# RMC_Backplane.net
KiCad netlist of a schematic drawn in Altium Designer
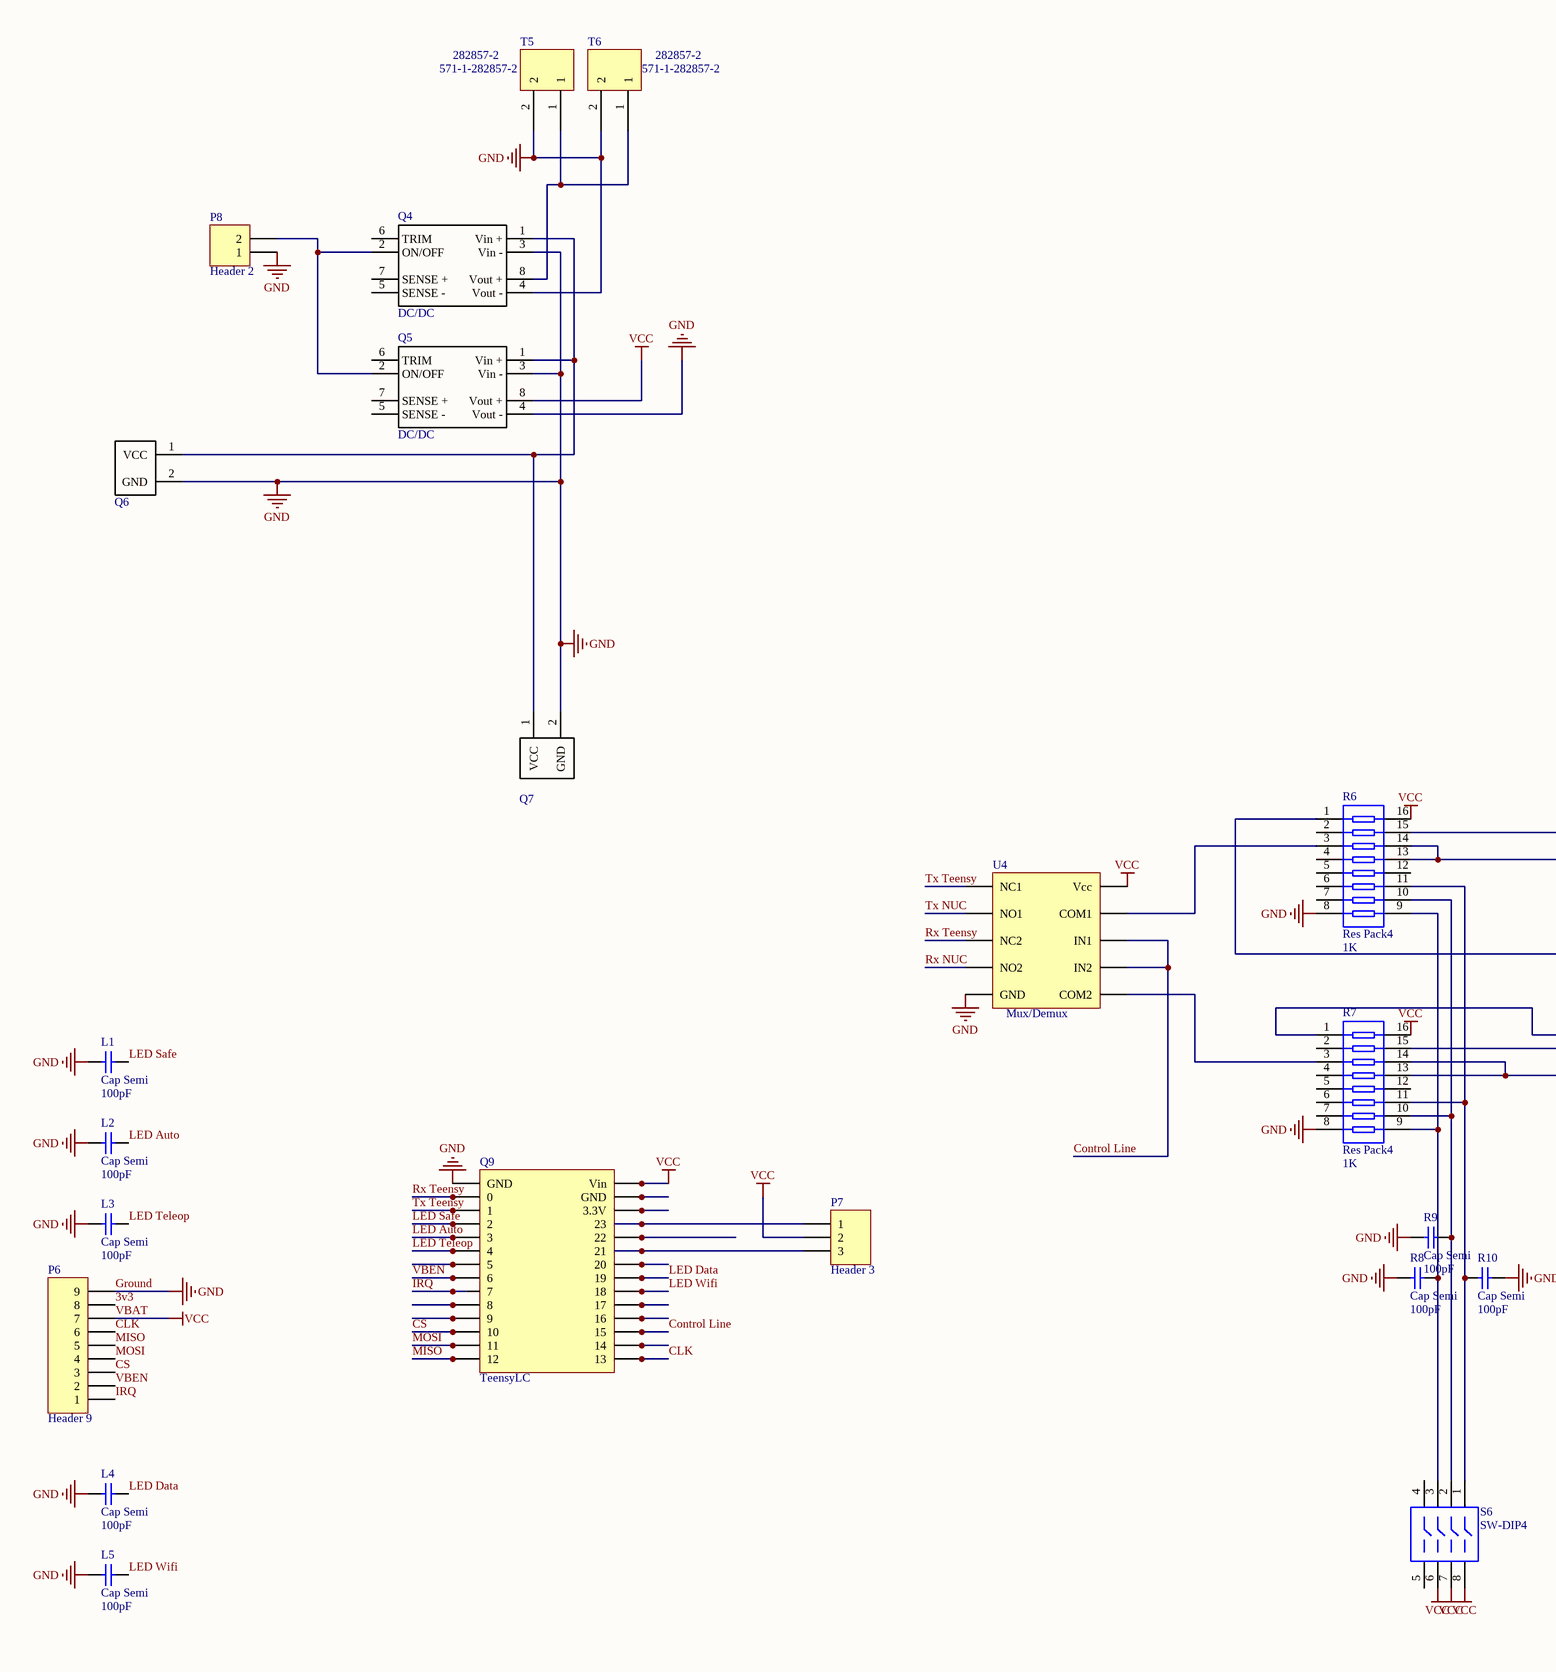
[diagram p0: RMC Backplane.SchDoc, left]
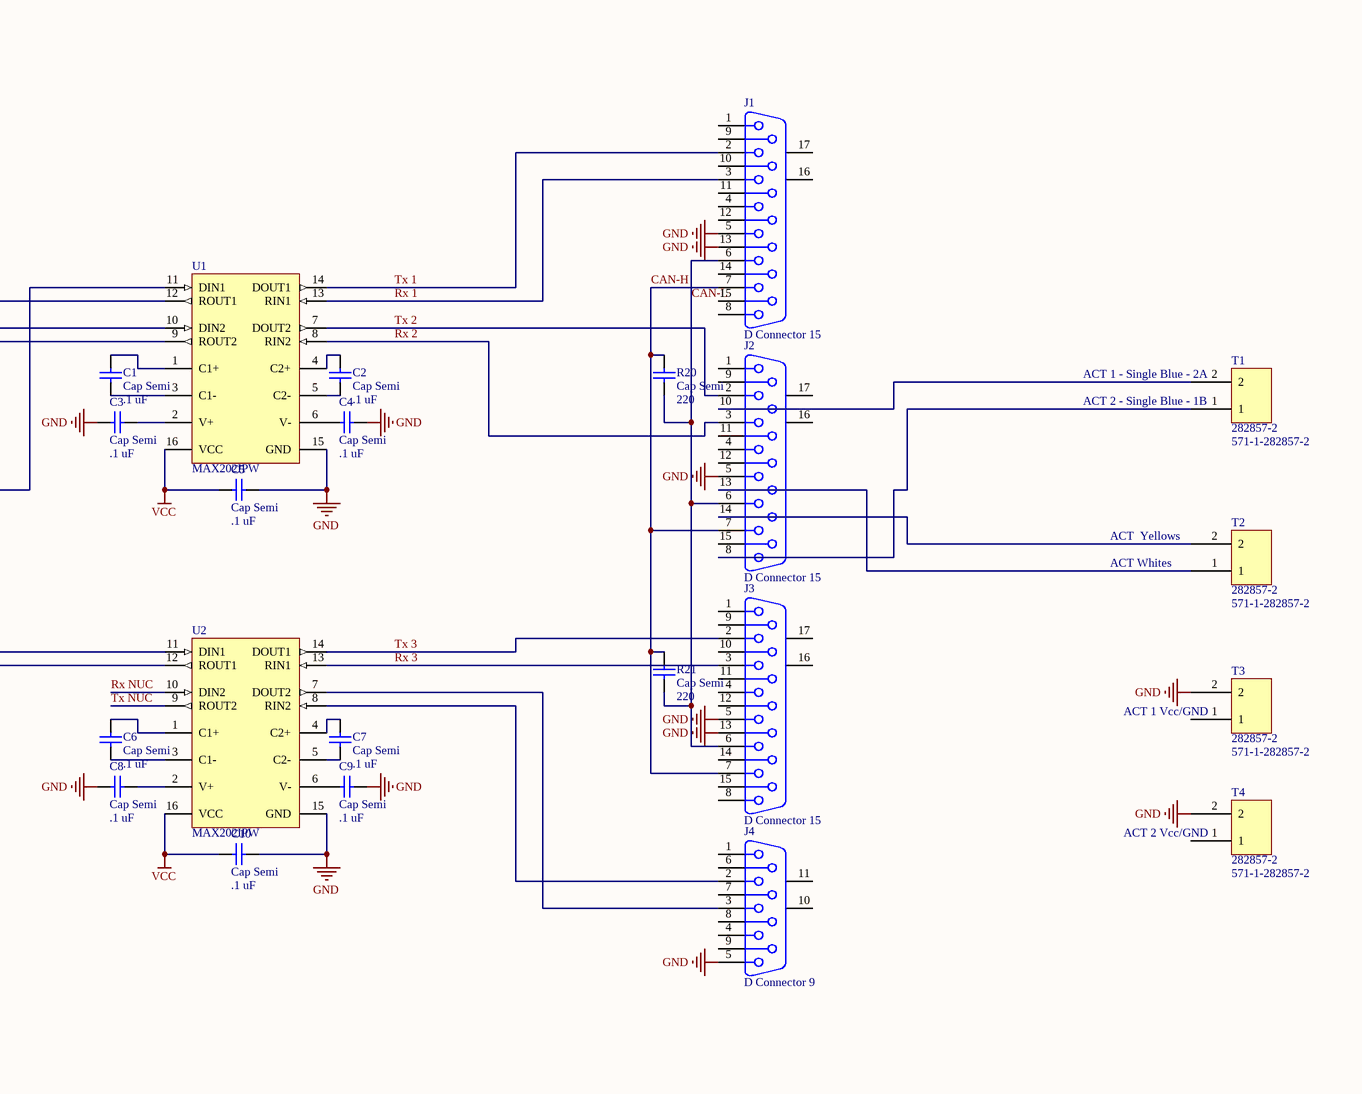
[diagram p1: RMC Backplane.SchDoc, right]

(export (version "E")
  (design (tool "Eeschema 10.0.6"))
  (components
    (comp (ref "C1")
      (value "Cap Semi")
      (footprint "C1206")
      (description "Capacitor (Semiconductor SIM Model)")
      (fields (field (name "ALTIUM_VALUE") ".1 uF") (field (name "PUBLISHER") "Altium Limited"))
      (libsource (lib "Miscellaneous Devices") (part "Cap Semi"))
    )
    (comp (ref "C2")
      (value "Cap Semi")
      (footprint "C1206")
      (description "Capacitor (Semiconductor SIM Model)")
      (fields (field (name "ALTIUM_VALUE") ".1 uF") (field (name "PUBLISHER") "Altium Limited"))
      (libsource (lib "Miscellaneous Devices") (part "Cap Semi"))
    )
    (comp (ref "C3")
      (value "Cap Semi")
      (footprint "C1206")
      (description "Capacitor (Semiconductor SIM Model)")
      (fields (field (name "ALTIUM_VALUE") ".1 uF") (field (name "PUBLISHER") "Altium Limited"))
      (libsource (lib "Miscellaneous Devices") (part "Cap Semi"))
    )
    (comp (ref "C4")
      (value "Cap Semi")
      (footprint "C1206")
      (description "Capacitor (Semiconductor SIM Model)")
      (fields (field (name "ALTIUM_VALUE") ".1 uF") (field (name "PUBLISHER") "Altium Limited"))
      (libsource (lib "Miscellaneous Devices") (part "Cap Semi"))
    )
    (comp (ref "C5")
      (value "Cap Semi")
      (footprint "C1206")
      (description "Capacitor (Semiconductor SIM Model)")
      (fields (field (name "ALTIUM_VALUE") ".1 uF") (field (name "PUBLISHER") "Altium Limited"))
      (libsource (lib "Miscellaneous Devices") (part "Cap Semi"))
    )
    (comp (ref "C6")
      (value "Cap Semi")
      (footprint "C1206")
      (description "Capacitor (Semiconductor SIM Model)")
      (fields (field (name "ALTIUM_VALUE") ".1 uF") (field (name "PUBLISHER") "Altium Limited"))
      (libsource (lib "Miscellaneous Devices") (part "Cap Semi"))
    )
    (comp (ref "C7")
      (value "Cap Semi")
      (footprint "C1206")
      (description "Capacitor (Semiconductor SIM Model)")
      (fields (field (name "ALTIUM_VALUE") ".1 uF") (field (name "PUBLISHER") "Altium Limited"))
      (libsource (lib "Miscellaneous Devices") (part "Cap Semi"))
    )
    (comp (ref "C8")
      (value "Cap Semi")
      (footprint "C1206")
      (description "Capacitor (Semiconductor SIM Model)")
      (fields (field (name "ALTIUM_VALUE") ".1 uF") (field (name "PUBLISHER") "Altium Limited"))
      (libsource (lib "Miscellaneous Devices") (part "Cap Semi"))
    )
    (comp (ref "C9")
      (value "Cap Semi")
      (footprint "C1206")
      (description "Capacitor (Semiconductor SIM Model)")
      (fields (field (name "ALTIUM_VALUE") ".1 uF") (field (name "PUBLISHER") "Altium Limited"))
      (libsource (lib "Miscellaneous Devices") (part "Cap Semi"))
    )
    (comp (ref "C10")
      (value "Cap Semi")
      (footprint "C1206")
      (description "Capacitor (Semiconductor SIM Model)")
      (fields (field (name "ALTIUM_VALUE") ".1 uF") (field (name "PUBLISHER") "Altium Limited"))
      (libsource (lib "Miscellaneous Devices") (part "Cap Semi"))
    )
    (comp (ref "J1")
      (value "D Connector 15")
      (footprint "DSUB1.385-2H15")
      (description "Receptacle Assembly, 15 Position, Right Angle")
      (fields (field (name "PUBLISHER") "Altium Limited"))
      (libsource (lib "Miscellaneous Connectors") (part "D Connector 15"))
    )
    (comp (ref "J2")
      (value "D Connector 15")
      (footprint "DSUB1.385-2H15")
      (description "Receptacle Assembly, 15 Position, Right Angle")
      (fields (field (name "PUBLISHER") "Altium Limited"))
      (libsource (lib "Miscellaneous Connectors") (part "D Connector 15"))
    )
    (comp (ref "J3")
      (value "D Connector 15")
      (footprint "DSUB1.385-2H15")
      (description "Receptacle Assembly, 15 Position, Right Angle")
      (fields (field (name "PUBLISHER") "Altium Limited"))
      (libsource (lib "Miscellaneous Connectors") (part "D Connector 15"))
    )
    (comp (ref "J4")
      (value "D Connector 9")
      (footprint "DSUB1.385-2H9")
      (description "Receptacle Assembly, 9 Position, Right Angle")
      (fields (field (name "PUBLISHER") "Altium Limited"))
      (libsource (lib "Miscellaneous Connectors") (part "D Connector 9"))
    )
    (comp (ref "L1")
      (value "Cap Semi")
      (footprint "C1206")
      (description "Capacitor (Semiconductor SIM Model)")
      (fields (field (name "ALTIUM_VALUE") "100pF") (field (name "PUBLISHER") "Altium Limited"))
      (libsource (lib "Miscellaneous Devices") (part "Cap Semi"))
    )
    (comp (ref "L2")
      (value "Cap Semi")
      (footprint "C1206")
      (description "Capacitor (Semiconductor SIM Model)")
      (fields (field (name "ALTIUM_VALUE") "100pF") (field (name "PUBLISHER") "Altium Limited"))
      (libsource (lib "Miscellaneous Devices") (part "Cap Semi"))
    )
    (comp (ref "L3")
      (value "Cap Semi")
      (footprint "C1206")
      (description "Capacitor (Semiconductor SIM Model)")
      (fields (field (name "ALTIUM_VALUE") "100pF") (field (name "PUBLISHER") "Altium Limited"))
      (libsource (lib "Miscellaneous Devices") (part "Cap Semi"))
    )
    (comp (ref "L4")
      (value "Cap Semi")
      (footprint "C1206")
      (description "Capacitor (Semiconductor SIM Model)")
      (fields (field (name "ALTIUM_VALUE") "100pF") (field (name "PUBLISHER") "Altium Limited"))
      (libsource (lib "Miscellaneous Devices") (part "Cap Semi"))
    )
    (comp (ref "L5")
      (value "Cap Semi")
      (footprint "C1206")
      (description "Capacitor (Semiconductor SIM Model)")
      (fields (field (name "ALTIUM_VALUE") "100pF") (field (name "PUBLISHER") "Altium Limited"))
      (libsource (lib "Miscellaneous Devices") (part "Cap Semi"))
    )
    (comp (ref "P6")
      (value "Header 9")
      (footprint "HDR1X9")
      (description "Header, 9-Pin")
      (fields (field (name "PUBLISHER") "Altium Limited"))
      (libsource (lib "Miscellaneous Connectors") (part "Header 9"))
    )
    (comp (ref "P7")
      (value "Header 3")
      (footprint "HDR1X3")
      (description "Header, 3-Pin")
      (fields (field (name "PUBLISHER") "Altium Limited"))
      (libsource (lib "Miscellaneous Connectors") (part "Header 3"))
    )
    (comp (ref "P8")
      (value "Header 2")
      (footprint "HDR1X2")
      (description "Header, 2-Pin")
      (fields (field (name "PUBLISHER") "Altium Limited"))
      (libsource (lib "Miscellaneous Connectors") (part "Header 2"))
    )
    (comp (ref "Q4")
      (value "DC/DC")
      (footprint "EHHD")
      (description "Voltage Regulator")
      (libsource (lib "Custom_Components") (part "EHHD"))
    )
    (comp (ref "Q5")
      (value "DC/DC")
      (footprint "EHHD")
      (description "Voltage Regulator")
      (libsource (lib "Custom_Components") (part "EHHD"))
    )
    (comp (ref "Q6")
      (value "Power Conn")
      (footprint "Mini-Fit Power Conn")
      (description "Mini-Fit Molex Connector")
      (libsource (lib "Custom_Schematics") (part "Mini-Fit Power Conn"))
    )
    (comp (ref "Q7")
      (value "Power Conn")
      (footprint "Mini-Fit Power Conn")
      (description "Mini-Fit Molex Connector")
      (libsource (lib "Custom_Schematics") (part "Mini-Fit Power Conn"))
    )
    (comp (ref "Q9")
      (value "TeensyLC")
      (footprint "TeensyLC")
      (libsource (lib "Custom_Schematics") (part "TeensyLC"))
    )
    (comp (ref "R6")
      (value "Res Pack4")
      (footprint "SSOP16_N")
      (description "Isolated Resistor Network")
      (fields (field (name "ALTIUM_VALUE") "1K") (field (name "PUBLISHER") "Altium Limited"))
      (libsource (lib "Miscellaneous Devices") (part "Res Pack4"))
    )
    (comp (ref "R7")
      (value "Res Pack4")
      (footprint "SSOP16_N")
      (description "Isolated Resistor Network")
      (fields (field (name "ALTIUM_VALUE") "1K") (field (name "PUBLISHER") "Altium Limited"))
      (libsource (lib "Miscellaneous Devices") (part "Res Pack4"))
    )
    (comp (ref "R8")
      (value "Cap Semi")
      (footprint "C1206")
      (description "Capacitor (Semiconductor SIM Model)")
      (fields (field (name "ALTIUM_VALUE") "100pF") (field (name "PUBLISHER") "Altium Limited"))
      (libsource (lib "Miscellaneous Devices") (part "Cap Semi"))
    )
    (comp (ref "R9")
      (value "Cap Semi")
      (footprint "C1206")
      (description "Capacitor (Semiconductor SIM Model)")
      (fields (field (name "ALTIUM_VALUE") "100pF") (field (name "PUBLISHER") "Altium Limited"))
      (libsource (lib "Miscellaneous Devices") (part "Cap Semi"))
    )
    (comp (ref "R10")
      (value "Cap Semi")
      (footprint "C1206")
      (description "Capacitor (Semiconductor SIM Model)")
      (fields (field (name "ALTIUM_VALUE") "100pF") (field (name "PUBLISHER") "Altium Limited"))
      (libsource (lib "Miscellaneous Devices") (part "Cap Semi"))
    )
    (comp (ref "R20")
      (value "Cap Semi")
      (footprint "C1206")
      (description "Capacitor (Semiconductor SIM Model)")
      (fields (field (name "ALTIUM_VALUE") "220") (field (name "PUBLISHER") "Altium Limited"))
      (libsource (lib "Miscellaneous Devices") (part "Cap Semi"))
    )
    (comp (ref "R21")
      (value "Cap Semi")
      (footprint "C1206")
      (description "Capacitor (Semiconductor SIM Model)")
      (fields (field (name "ALTIUM_VALUE") "220") (field (name "PUBLISHER") "Altium Limited"))
      (libsource (lib "Miscellaneous Devices") (part "Cap Semi"))
    )
    (comp (ref "S6")
      (value "SW-DIP4")
      (footprint "DIP-8")
      (description "DIP Switch")
      (fields (field (name "PUBLISHER") "Altium Limited"))
      (libsource (lib "Miscellaneous Devices") (part "SW-DIP4"))
    )
    (comp (ref "T1")
      (value "282857-2")
      (footprint "282857-2")
      (fields (field (name "SUPPLIER PART NUMBER 1") "571-1-282857-2"))
      (libsource (lib "") (part "282857-2_1"))
    )
    (comp (ref "T2")
      (value "282857-2")
      (footprint "282857-2")
      (fields (field (name "SUPPLIER PART NUMBER 1") "571-1-282857-2"))
      (libsource (lib "") (part "282857-2_1"))
    )
    (comp (ref "T3")
      (value "282857-2")
      (footprint "282857-2")
      (fields (field (name "SUPPLIER PART NUMBER 1") "571-1-282857-2"))
      (libsource (lib "") (part "282857-2_1"))
    )
    (comp (ref "T4")
      (value "282857-2")
      (footprint "282857-2")
      (fields (field (name "SUPPLIER PART NUMBER 1") "571-1-282857-2"))
      (libsource (lib "") (part "282857-2_1"))
    )
    (comp (ref "T5")
      (value "282857-2")
      (footprint "282857-2")
      (fields (field (name "SUPPLIER PART NUMBER 1") "571-1-282857-2"))
      (libsource (lib "TE_Connectors") (part "282857-2"))
    )
    (comp (ref "T6")
      (value "282857-2")
      (footprint "282857-2")
      (fields (field (name "SUPPLIER PART NUMBER 1") "571-1-282857-2"))
      (libsource (lib "TE_Connectors") (part "282857-2"))
    )
    (comp (ref "U1")
      (value "MAX202IPW")
      (footprint "TI-PW16_N")
      (libsource (lib "Texas Instruments Interface RS-232") (part "MAX202IPW"))
    )
    (comp (ref "U2")
      (value "MAX202IPW")
      (footprint "TI-PW16_N")
      (libsource (lib "Texas Instruments Interface RS-232") (part "MAX202IPW"))
    )
    (comp (ref "U4")
      (value "Mux/Demux")
      (footprint "TS3A24157")
      (libsource (lib "Custom_Schematics") (part "Mux/Demux"))
    )
  )
  (nets
    (net (code "1") (name "/3v3") (class "Default")
      (node (ref "P6") (pin "8") (pinfunction "8_8") (pintype "passive"))
    )
    (net (code "2") (name "/CAN-H") (class "Default")
      (node (ref "J1") (pin "7") (pinfunction "7_7") (pintype "passive"))
      (node (ref "J2") (pin "7") (pinfunction "7_7") (pintype "passive"))
      (node (ref "J3") (pin "7") (pinfunction "7_7") (pintype "passive"))
      (node (ref "R20") (pin "1") (pinfunction "1_1") (pintype "passive"))
      (node (ref "R21") (pin "1") (pinfunction "1_1") (pintype "passive"))
    )
    (net (code "3") (name "/CAN-L") (class "Default")
      (node (ref "J1") (pin "6") (pinfunction "6_6") (pintype "passive"))
      (node (ref "J2") (pin "6") (pinfunction "6_6") (pintype "passive"))
      (node (ref "J3") (pin "6") (pinfunction "6_6") (pintype "passive"))
      (node (ref "R20") (pin "2") (pinfunction "2_2") (pintype "passive"))
      (node (ref "R21") (pin "2") (pinfunction "2_2") (pintype "passive"))
    )
    (net (code "4") (name "/CLK") (class "Default")
      (node (ref "P6") (pin "6") (pinfunction "6_6") (pintype "passive"))
      (node (ref "Q9") (pin "15") (pinfunction "13_15") (pintype "passive"))
    )
    (net (code "5") (name "/CS") (class "Default")
      (node (ref "P6") (pin "3") (pinfunction "3_3") (pintype "passive"))
      (node (ref "Q9") (pin "12") (pinfunction "10_12") (pintype "passive"))
    )
    (net (code "6") (name "/Control Line") (class "Default")
      (node (ref "Q9") (pin "17") (pinfunction "15_17") (pintype "passive"))
      (node (ref "U4") (pin "7") (pinfunction "IN2_7") (pintype "passive"))
      (node (ref "U4") (pin "8") (pinfunction "IN1_8") (pintype "passive"))
    )
    (net (code "7") (name "/IRQ") (class "Default")
      (node (ref "P6") (pin "1") (pinfunction "1_1") (pintype "passive"))
      (node (ref "Q9") (pin "9") (pinfunction "7_9") (pintype "passive"))
    )
    (net (code "8") (name "/LED Auto") (class "Default")
      (node (ref "L2") (pin "2") (pinfunction "2_2") (pintype "passive"))
      (node (ref "Q9") (pin "5") (pinfunction "3_5") (pintype "passive"))
    )
    (net (code "9") (name "/LED Data") (class "Default")
      (node (ref "L4") (pin "2") (pinfunction "2_2") (pintype "passive"))
      (node (ref "Q9") (pin "21") (pinfunction "19_21") (pintype "passive"))
    )
    (net (code "10") (name "/LED Safe") (class "Default")
      (node (ref "L1") (pin "2") (pinfunction "2_2") (pintype "passive"))
      (node (ref "Q9") (pin "4") (pinfunction "2_4") (pintype "passive"))
    )
    (net (code "11") (name "/LED Teleop") (class "Default")
      (node (ref "L3") (pin "2") (pinfunction "2_2") (pintype "passive"))
      (node (ref "Q9") (pin "6") (pinfunction "4_6") (pintype "passive"))
    )
    (net (code "12") (name "/LED Wifi") (class "Default")
      (node (ref "L5") (pin "2") (pinfunction "2_2") (pintype "passive"))
      (node (ref "Q9") (pin "20") (pinfunction "18_20") (pintype "passive"))
    )
    (net (code "13") (name "/MISO") (class "Default")
      (node (ref "P6") (pin "5") (pinfunction "5_5") (pintype "passive"))
      (node (ref "Q9") (pin "14") (pinfunction "12_14") (pintype "passive"))
    )
    (net (code "14") (name "/MOSI") (class "Default")
      (node (ref "P6") (pin "4") (pinfunction "4_4") (pintype "passive"))
      (node (ref "Q9") (pin "13") (pinfunction "11_13") (pintype "passive"))
    )
    (net (code "15") (name "/Rx 1") (class "Default")
      (node (ref "J1") (pin "3") (pinfunction "3_3") (pintype "passive"))
      (node (ref "U1") (pin "13") (pinfunction "RIN1_13") (pintype "input"))
    )
    (net (code "16") (name "/Rx 2") (class "Default")
      (node (ref "J2") (pin "3") (pinfunction "3_3") (pintype "passive"))
      (node (ref "U1") (pin "8") (pinfunction "RIN2_8") (pintype "input"))
    )
    (net (code "17") (name "/Rx 3") (class "Default")
      (node (ref "J3") (pin "3") (pinfunction "3_3") (pintype "passive"))
      (node (ref "U2") (pin "13") (pinfunction "RIN1_13") (pintype "input"))
    )
    (net (code "18") (name "/Rx NUC") (class "Default")
      (node (ref "U2") (pin "10") (pinfunction "DIN2_10") (pintype "input"))
      (node (ref "U4") (pin "4") (pinfunction "NO2_4") (pintype "passive"))
    )
    (net (code "19") (name "/Rx Teensy") (class "Default")
      (node (ref "Q9") (pin "2") (pinfunction "0_2") (pintype "passive"))
      (node (ref "U4") (pin "3") (pinfunction "NC2_3") (pintype "passive"))
    )
    (net (code "20") (name "/Tx 1") (class "Default")
      (node (ref "J1") (pin "2") (pinfunction "2_2") (pintype "passive"))
      (node (ref "U1") (pin "14") (pinfunction "DOUT1_14") (pintype "output"))
    )
    (net (code "21") (name "/Tx 2") (class "Default")
      (node (ref "J2") (pin "2") (pinfunction "2_2") (pintype "passive"))
      (node (ref "U1") (pin "7") (pinfunction "DOUT2_7") (pintype "output"))
    )
    (net (code "22") (name "/Tx 3") (class "Default")
      (node (ref "J3") (pin "2") (pinfunction "2_2") (pintype "passive"))
      (node (ref "U2") (pin "14") (pinfunction "DOUT1_14") (pintype "output"))
    )
    (net (code "23") (name "/Tx NUC") (class "Default")
      (node (ref "U2") (pin "9") (pinfunction "ROUT2_9") (pintype "output"))
      (node (ref "U4") (pin "2") (pinfunction "NO1_2") (pintype "passive"))
    )
    (net (code "24") (name "/Tx Teensy") (class "Default")
      (node (ref "Q9") (pin "3") (pinfunction "1_3") (pintype "passive"))
      (node (ref "U4") (pin "1") (pinfunction "NC1_1") (pintype "passive"))
    )
    (net (code "25") (name "/VBEN") (class "Default")
      (node (ref "P6") (pin "2") (pinfunction "2_2") (pintype "passive"))
      (node (ref "Q9") (pin "8") (pinfunction "6_8") (pintype "passive"))
    )
    (net (code "26") (name "GND") (class "Default")
      (node (ref "C10") (pin "2") (pinfunction "2_2") (pintype "passive"))
      (node (ref "C3") (pin "1") (pinfunction "1_1") (pintype "passive"))
      (node (ref "C4") (pin "2") (pinfunction "2_2") (pintype "passive"))
      (node (ref "C5") (pin "2") (pinfunction "2_2") (pintype "passive"))
      (node (ref "C8") (pin "1") (pinfunction "1_1") (pintype "passive"))
      (node (ref "C9") (pin "2") (pinfunction "2_2") (pintype "passive"))
      (node (ref "J1") (pin "13") (pinfunction "13_13") (pintype "passive"))
      (node (ref "J1") (pin "5") (pinfunction "5_5") (pintype "passive"))
      (node (ref "J2") (pin "5") (pinfunction "5_5") (pintype "passive"))
      (node (ref "J3") (pin "13") (pinfunction "13_13") (pintype "passive"))
      (node (ref "J3") (pin "5") (pinfunction "5_5") (pintype "passive"))
      (node (ref "J4") (pin "5") (pinfunction "5_5") (pintype "passive"))
      (node (ref "L1") (pin "1") (pinfunction "1_1") (pintype "passive"))
      (node (ref "L2") (pin "1") (pinfunction "1_1") (pintype "passive"))
      (node (ref "L3") (pin "1") (pinfunction "1_1") (pintype "passive"))
      (node (ref "L4") (pin "1") (pinfunction "1_1") (pintype "passive"))
      (node (ref "L5") (pin "1") (pinfunction "1_1") (pintype "passive"))
      (node (ref "P6") (pin "9") (pinfunction "9_9") (pintype "passive"))
      (node (ref "P8") (pin "1") (pinfunction "1_1") (pintype "passive"))
      (node (ref "Q4") (pin "3") (pinfunction "Vin_-_3") (pintype "passive"))
      (node (ref "Q4") (pin "4") (pinfunction "Vout_-_4") (pintype "power_in"))
      (node (ref "Q5") (pin "3") (pinfunction "Vin_-_3") (pintype "passive"))
      (node (ref "Q5") (pin "4") (pinfunction "Vout_-_4") (pintype "power_in"))
      (node (ref "Q6") (pin "2") (pinfunction "GND_2") (pintype "power_in"))
      (node (ref "Q7") (pin "2") (pinfunction "GND_2") (pintype "power_in"))
      (node (ref "Q9") (pin "1") (pinfunction "GND_1") (pintype "passive"))
      (node (ref "R10") (pin "2") (pinfunction "2_2") (pintype "passive"))
      (node (ref "R6") (pin "8") (pinfunction "8_8") (pintype "passive"))
      (node (ref "R7") (pin "8") (pinfunction "8_8") (pintype "passive"))
      (node (ref "R8") (pin "1") (pinfunction "1_1") (pintype "passive"))
      (node (ref "R9") (pin "1") (pinfunction "1_1") (pintype "passive"))
      (node (ref "T3") (pin "2") (pinfunction "2_2") (pintype "passive"))
      (node (ref "T4") (pin "2") (pinfunction "2_2") (pintype "passive"))
      (node (ref "T5") (pin "2") (pinfunction "2_2") (pintype "passive"))
      (node (ref "T6") (pin "2") (pinfunction "2_2") (pintype "passive"))
      (node (ref "U1") (pin "15") (pinfunction "GND_15") (pintype "power_in"))
      (node (ref "U2") (pin "15") (pinfunction "GND_15") (pintype "power_in"))
      (node (ref "U4") (pin "5") (pinfunction "GND_5") (pintype "passive"))
    )
    (net (code "27") (name "Net-(J2-Pad8)") (class "Default")
      (node (ref "J2") (pin "8") (pinfunction "8_8") (pintype "passive"))
      (node (ref "T1") (pin "1") (pinfunction "1_1") (pintype "passive"))
    )
    (net (code "28") (name "Net-(J2-Pad10)") (class "Default")
      (node (ref "J2") (pin "10") (pinfunction "10_10") (pintype "passive"))
      (node (ref "T1") (pin "2") (pinfunction "2_2") (pintype "passive"))
    )
    (net (code "29") (name "Net-(J2-Pad13)") (class "Default")
      (node (ref "J2") (pin "13") (pinfunction "13_13") (pintype "passive"))
      (node (ref "T2") (pin "1") (pinfunction "1_1") (pintype "passive"))
    )
    (net (code "30") (name "Net-(J2-Pad14)") (class "Default")
      (node (ref "J2") (pin "14") (pinfunction "14_14") (pintype "passive"))
      (node (ref "T2") (pin "2") (pinfunction "2_2") (pintype "passive"))
    )
    (net (code "31") (name "Net-(Q4-ON{slash}OFF)") (class "Default")
      (node (ref "P8") (pin "2") (pinfunction "2_2") (pintype "passive"))
      (node (ref "Q4") (pin "2") (pinfunction "ON/OFF_2") (pintype "passive"))
      (node (ref "Q5") (pin "2") (pinfunction "ON/OFF_2") (pintype "passive"))
    )
    (net (code "32") (name "Net-(Q4-Vin_+)") (class "Default")
      (node (ref "Q4") (pin "1") (pinfunction "Vin_+_1") (pintype "passive"))
      (node (ref "Q5") (pin "1") (pinfunction "Vin_+_1") (pintype "passive"))
      (node (ref "Q6") (pin "1") (pinfunction "VCC_1") (pintype "power_in"))
      (node (ref "Q7") (pin "1") (pinfunction "VCC_1") (pintype "power_in"))
    )
    (net (code "33") (name "Net-(Q4-Vout_+)") (class "Default")
      (node (ref "Q4") (pin "8") (pinfunction "Vout_+_8") (pintype "power_in"))
      (node (ref "T5") (pin "1") (pinfunction "1_1") (pintype "passive"))
      (node (ref "T6") (pin "1") (pinfunction "1_1") (pintype "passive"))
    )
    (net (code "34") (name "Net-(Q9-21)") (class "Default")
      (node (ref "P7") (pin "3") (pinfunction "3_3") (pintype "passive"))
      (node (ref "Q9") (pin "23") (pinfunction "21_23") (pintype "passive"))
    )
    (net (code "35") (name "Net-(Q9-23)") (class "Default")
      (node (ref "P7") (pin "1") (pinfunction "1_1") (pintype "passive"))
      (node (ref "Q9") (pin "25") (pinfunction "23_25") (pintype "passive"))
    )
    (net (code "36") (name "Net-(R6-Pad9)") (class "Default")
      (node (ref "R6") (pin "9") (pinfunction "9_9") (pintype "passive"))
      (node (ref "R7") (pin "9") (pinfunction "9_9") (pintype "passive"))
      (node (ref "R8") (pin "2") (pinfunction "2_2") (pintype "passive"))
      (node (ref "S6") (pin "3") (pinfunction "3_3") (pintype "passive"))
    )
    (net (code "37") (name "Net-(R6-Pad10)") (class "Default")
      (node (ref "R6") (pin "10") (pinfunction "10_10") (pintype "passive"))
      (node (ref "R7") (pin "10") (pinfunction "10_10") (pintype "passive"))
      (node (ref "R9") (pin "2") (pinfunction "2_2") (pintype "passive"))
      (node (ref "S6") (pin "2") (pinfunction "2_2") (pintype "passive"))
    )
    (net (code "38") (name "Net-(R10-Pad1)") (class "Default")
      (node (ref "R10") (pin "1") (pinfunction "1_1") (pintype "passive"))
      (node (ref "R6") (pin "11") (pinfunction "11_11") (pintype "passive"))
      (node (ref "R7") (pin "11") (pinfunction "11_11") (pintype "passive"))
      (node (ref "S6") (pin "1") (pinfunction "1_1") (pintype "passive"))
    )
    (net (code "39") (name "Net-(U1-C1+)") (class "Default")
      (node (ref "C1") (pin "1") (pinfunction "1_1") (pintype "passive"))
      (node (ref "U1") (pin "1") (pinfunction "C1+_1") (pintype "passive"))
    )
    (net (code "40") (name "Net-(U1-C1-)") (class "Default")
      (node (ref "C1") (pin "2") (pinfunction "2_2") (pintype "passive"))
      (node (ref "U1") (pin "3") (pinfunction "C1-_3") (pintype "passive"))
    )
    (net (code "41") (name "Net-(U1-C2+)") (class "Default")
      (node (ref "C2") (pin "1") (pinfunction "1_1") (pintype "passive"))
      (node (ref "U1") (pin "4") (pinfunction "C2+_4") (pintype "passive"))
    )
    (net (code "42") (name "Net-(U1-C2-)") (class "Default")
      (node (ref "C2") (pin "2") (pinfunction "2_2") (pintype "passive"))
      (node (ref "U1") (pin "5") (pinfunction "C2-_5") (pintype "passive"))
    )
    (net (code "43") (name "Net-(U1-DIN1)") (class "Default")
      (node (ref "R6") (pin "13") (pinfunction "13_13") (pintype "passive"))
      (node (ref "R6") (pin "14") (pinfunction "14_14") (pintype "passive"))
      (node (ref "U1") (pin "11") (pinfunction "DIN1_11") (pintype "input"))
    )
    (net (code "44") (name "Net-(U1-DIN2)") (class "Default")
      (node (ref "R6") (pin "15") (pinfunction "15_15") (pintype "passive"))
      (node (ref "U1") (pin "10") (pinfunction "DIN2_10") (pintype "input"))
    )
    (net (code "45") (name "Net-(U1-ROUT1)") (class "Default")
      (node (ref "R7") (pin "13") (pinfunction "13_13") (pintype "passive"))
      (node (ref "R7") (pin "14") (pinfunction "14_14") (pintype "passive"))
      (node (ref "U1") (pin "12") (pinfunction "ROUT1_12") (pintype "output"))
    )
    (net (code "46") (name "Net-(U1-ROUT2)") (class "Default")
      (node (ref "R7") (pin "15") (pinfunction "15_15") (pintype "passive"))
      (node (ref "U1") (pin "9") (pinfunction "ROUT2_9") (pintype "output"))
    )
    (net (code "47") (name "Net-(U1-V+)") (class "Default")
      (node (ref "C3") (pin "2") (pinfunction "2_2") (pintype "passive"))
      (node (ref "U1") (pin "2") (pinfunction "V+_2") (pintype "power_in"))
    )
    (net (code "48") (name "Net-(U1-V-)") (class "Default")
      (node (ref "C4") (pin "1") (pinfunction "1_1") (pintype "passive"))
      (node (ref "U1") (pin "6") (pinfunction "V-_6") (pintype "power_in"))
    )
    (net (code "49") (name "Net-(U2-C1+)") (class "Default")
      (node (ref "C6") (pin "1") (pinfunction "1_1") (pintype "passive"))
      (node (ref "U2") (pin "1") (pinfunction "C1+_1") (pintype "passive"))
    )
    (net (code "50") (name "Net-(U2-C1-)") (class "Default")
      (node (ref "C6") (pin "2") (pinfunction "2_2") (pintype "passive"))
      (node (ref "U2") (pin "3") (pinfunction "C1-_3") (pintype "passive"))
    )
    (net (code "51") (name "Net-(U2-C2+)") (class "Default")
      (node (ref "C7") (pin "1") (pinfunction "1_1") (pintype "passive"))
      (node (ref "U2") (pin "4") (pinfunction "C2+_4") (pintype "passive"))
    )
    (net (code "52") (name "Net-(U2-C2-)") (class "Default")
      (node (ref "C7") (pin "2") (pinfunction "2_2") (pintype "passive"))
      (node (ref "U2") (pin "5") (pinfunction "C2-_5") (pintype "passive"))
    )
    (net (code "53") (name "Net-(U2-DIN1)") (class "Default")
      (node (ref "R6") (pin "1") (pinfunction "1_1") (pintype "passive"))
      (node (ref "U2") (pin "11") (pinfunction "DIN1_11") (pintype "input"))
    )
    (net (code "54") (name "Net-(U2-DOUT2)") (class "Default")
      (node (ref "J4") (pin "3") (pinfunction "3_3") (pintype "passive"))
      (node (ref "U2") (pin "7") (pinfunction "DOUT2_7") (pintype "output"))
    )
    (net (code "55") (name "Net-(U2-RIN2)") (class "Default")
      (node (ref "J4") (pin "2") (pinfunction "2_2") (pintype "passive"))
      (node (ref "U2") (pin "8") (pinfunction "RIN2_8") (pintype "input"))
    )
    (net (code "56") (name "Net-(U2-ROUT1)") (class "Default")
      (node (ref "R7") (pin "1") (pinfunction "1_1") (pintype "passive"))
      (node (ref "U2") (pin "12") (pinfunction "ROUT1_12") (pintype "output"))
    )
    (net (code "57") (name "Net-(U2-V+)") (class "Default")
      (node (ref "C8") (pin "2") (pinfunction "2_2") (pintype "passive"))
      (node (ref "U2") (pin "2") (pinfunction "V+_2") (pintype "power_in"))
    )
    (net (code "58") (name "Net-(U2-V-)") (class "Default")
      (node (ref "C9") (pin "1") (pinfunction "1_1") (pintype "passive"))
      (node (ref "U2") (pin "6") (pinfunction "V-_6") (pintype "power_in"))
    )
    (net (code "59") (name "Net-(U4-COM1)") (class "Default")
      (node (ref "R6") (pin "3") (pinfunction "3_3") (pintype "passive"))
      (node (ref "U4") (pin "9") (pinfunction "COM1_9") (pintype "passive"))
    )
    (net (code "60") (name "Net-(U4-COM2)") (class "Default")
      (node (ref "R7") (pin "3") (pinfunction "3_3") (pintype "passive"))
      (node (ref "U4") (pin "6") (pinfunction "COM2_6") (pintype "passive"))
    )
    (net (code "61") (name "VCC") (class "Default")
      (node (ref "C10") (pin "1") (pinfunction "1_1") (pintype "passive"))
      (node (ref "C5") (pin "1") (pinfunction "1_1") (pintype "passive"))
      (node (ref "P6") (pin "7") (pinfunction "7_7") (pintype "passive"))
      (node (ref "P7") (pin "2") (pinfunction "2_2") (pintype "passive"))
      (node (ref "Q5") (pin "8") (pinfunction "Vout_+_8") (pintype "power_in"))
      (node (ref "Q9") (pin "28") (pinfunction "Vin_28") (pintype "passive"))
      (node (ref "R6") (pin "16") (pinfunction "16_16") (pintype "passive"))
      (node (ref "R7") (pin "16") (pinfunction "16_16") (pintype "passive"))
      (node (ref "S6") (pin "6") (pinfunction "6_6") (pintype "passive"))
      (node (ref "S6") (pin "7") (pinfunction "7_7") (pintype "passive"))
      (node (ref "S6") (pin "8") (pinfunction "8_8") (pintype "passive"))
      (node (ref "U1") (pin "16") (pinfunction "VCC_16") (pintype "power_in"))
      (node (ref "U2") (pin "16") (pinfunction "VCC_16") (pintype "power_in"))
      (node (ref "U4") (pin "10") (pinfunction "Vcc_10") (pintype "passive"))
    )
    (net (code "62") (name "unconnected-(J1-MH1-Pad16)") (class "Default")
      (node (ref "J1") (pin "16") (pinfunction "MH1_16") (pintype "passive"))
    )
    (net (code "63") (name "unconnected-(J1-MH2-Pad17)") (class "Default")
      (node (ref "J1") (pin "17") (pinfunction "MH2_17") (pintype "passive"))
    )
    (net (code "64") (name "unconnected-(J1-Pad1)") (class "Default")
      (node (ref "J1") (pin "1") (pinfunction "1_1") (pintype "passive"))
    )
    (net (code "65") (name "unconnected-(J1-Pad4)") (class "Default")
      (node (ref "J1") (pin "4") (pinfunction "4_4") (pintype "passive"))
    )
    (net (code "66") (name "unconnected-(J1-Pad8)") (class "Default")
      (node (ref "J1") (pin "8") (pinfunction "8_8") (pintype "passive"))
    )
    (net (code "67") (name "unconnected-(J1-Pad9)") (class "Default")
      (node (ref "J1") (pin "9") (pinfunction "9_9") (pintype "passive"))
    )
    (net (code "68") (name "unconnected-(J1-Pad10)") (class "Default")
      (node (ref "J1") (pin "10") (pinfunction "10_10") (pintype "passive"))
    )
    (net (code "69") (name "unconnected-(J1-Pad11)") (class "Default")
      (node (ref "J1") (pin "11") (pinfunction "11_11") (pintype "passive"))
    )
    (net (code "70") (name "unconnected-(J1-Pad12)") (class "Default")
      (node (ref "J1") (pin "12") (pinfunction "12_12") (pintype "passive"))
    )
    (net (code "71") (name "unconnected-(J1-Pad14)") (class "Default")
      (node (ref "J1") (pin "14") (pinfunction "14_14") (pintype "passive"))
    )
    (net (code "72") (name "unconnected-(J1-Pad15)") (class "Default")
      (node (ref "J1") (pin "15") (pinfunction "15_15") (pintype "passive"))
    )
    (net (code "73") (name "unconnected-(J2-MH1-Pad16)") (class "Default")
      (node (ref "J2") (pin "16") (pinfunction "MH1_16") (pintype "passive"))
    )
    (net (code "74") (name "unconnected-(J2-MH2-Pad17)") (class "Default")
      (node (ref "J2") (pin "17") (pinfunction "MH2_17") (pintype "passive"))
    )
    (net (code "75") (name "unconnected-(J2-Pad1)") (class "Default")
      (node (ref "J2") (pin "1") (pinfunction "1_1") (pintype "passive"))
    )
    (net (code "76") (name "unconnected-(J2-Pad4)") (class "Default")
      (node (ref "J2") (pin "4") (pinfunction "4_4") (pintype "passive"))
    )
    (net (code "77") (name "unconnected-(J2-Pad9)") (class "Default")
      (node (ref "J2") (pin "9") (pinfunction "9_9") (pintype "passive"))
    )
    (net (code "78") (name "unconnected-(J2-Pad11)") (class "Default")
      (node (ref "J2") (pin "11") (pinfunction "11_11") (pintype "passive"))
    )
    (net (code "79") (name "unconnected-(J2-Pad12)") (class "Default")
      (node (ref "J2") (pin "12") (pinfunction "12_12") (pintype "passive"))
    )
    (net (code "80") (name "unconnected-(J2-Pad15)") (class "Default")
      (node (ref "J2") (pin "15") (pinfunction "15_15") (pintype "passive"))
    )
    (net (code "81") (name "unconnected-(J3-MH1-Pad16)") (class "Default")
      (node (ref "J3") (pin "16") (pinfunction "MH1_16") (pintype "passive"))
    )
    (net (code "82") (name "unconnected-(J3-MH2-Pad17)") (class "Default")
      (node (ref "J3") (pin "17") (pinfunction "MH2_17") (pintype "passive"))
    )
    (net (code "83") (name "unconnected-(J3-Pad1)") (class "Default")
      (node (ref "J3") (pin "1") (pinfunction "1_1") (pintype "passive"))
    )
    (net (code "84") (name "unconnected-(J3-Pad4)") (class "Default")
      (node (ref "J3") (pin "4") (pinfunction "4_4") (pintype "passive"))
    )
    (net (code "85") (name "unconnected-(J3-Pad8)") (class "Default")
      (node (ref "J3") (pin "8") (pinfunction "8_8") (pintype "passive"))
    )
    (net (code "86") (name "unconnected-(J3-Pad9)") (class "Default")
      (node (ref "J3") (pin "9") (pinfunction "9_9") (pintype "passive"))
    )
    (net (code "87") (name "unconnected-(J3-Pad10)") (class "Default")
      (node (ref "J3") (pin "10") (pinfunction "10_10") (pintype "passive"))
    )
    (net (code "88") (name "unconnected-(J3-Pad11)") (class "Default")
      (node (ref "J3") (pin "11") (pinfunction "11_11") (pintype "passive"))
    )
    (net (code "89") (name "unconnected-(J3-Pad12)") (class "Default")
      (node (ref "J3") (pin "12") (pinfunction "12_12") (pintype "passive"))
    )
    (net (code "90") (name "unconnected-(J3-Pad14)") (class "Default")
      (node (ref "J3") (pin "14") (pinfunction "14_14") (pintype "passive"))
    )
    (net (code "91") (name "unconnected-(J3-Pad15)") (class "Default")
      (node (ref "J3") (pin "15") (pinfunction "15_15") (pintype "passive"))
    )
    (net (code "92") (name "unconnected-(J4-MH1-Pad10)") (class "Default")
      (node (ref "J4") (pin "10") (pinfunction "MH1_10") (pintype "passive"))
    )
    (net (code "93") (name "unconnected-(J4-MH2-Pad11)") (class "Default")
      (node (ref "J4") (pin "11") (pinfunction "MH2_11") (pintype "passive"))
    )
    (net (code "94") (name "unconnected-(J4-Pad1)") (class "Default")
      (node (ref "J4") (pin "1") (pinfunction "1_1") (pintype "passive"))
    )
    (net (code "95") (name "unconnected-(J4-Pad4)") (class "Default")
      (node (ref "J4") (pin "4") (pinfunction "4_4") (pintype "passive"))
    )
    (net (code "96") (name "unconnected-(J4-Pad6)") (class "Default")
      (node (ref "J4") (pin "6") (pinfunction "6_6") (pintype "passive"))
    )
    (net (code "97") (name "unconnected-(J4-Pad7)") (class "Default")
      (node (ref "J4") (pin "7") (pinfunction "7_7") (pintype "passive"))
    )
    (net (code "98") (name "unconnected-(J4-Pad8)") (class "Default")
      (node (ref "J4") (pin "8") (pinfunction "8_8") (pintype "passive"))
    )
    (net (code "99") (name "unconnected-(J4-Pad9)") (class "Default")
      (node (ref "J4") (pin "9") (pinfunction "9_9") (pintype "passive"))
    )
    (net (code "100") (name "unconnected-(Q4-SENSE_+-Pad7)") (class "Default")
      (node (ref "Q4") (pin "7") (pinfunction "SENSE_+_7") (pintype "passive"))
    )
    (net (code "101") (name "unconnected-(Q4-SENSE_--Pad5)") (class "Default")
      (node (ref "Q4") (pin "5") (pinfunction "SENSE_-_5") (pintype "passive"))
    )
    (net (code "102") (name "unconnected-(Q4-TRIM-Pad6)") (class "Default")
      (node (ref "Q4") (pin "6") (pinfunction "TRIM_6") (pintype "passive"))
    )
    (net (code "103") (name "unconnected-(Q5-SENSE_+-Pad7)") (class "Default")
      (node (ref "Q5") (pin "7") (pinfunction "SENSE_+_7") (pintype "passive"))
    )
    (net (code "104") (name "unconnected-(Q5-SENSE_--Pad5)") (class "Default")
      (node (ref "Q5") (pin "5") (pinfunction "SENSE_-_5") (pintype "passive"))
    )
    (net (code "105") (name "unconnected-(Q5-TRIM-Pad6)") (class "Default")
      (node (ref "Q5") (pin "6") (pinfunction "TRIM_6") (pintype "passive"))
    )
    (net (code "106") (name "unconnected-(Q9-3.3V-Pad26)") (class "Default")
      (node (ref "Q9") (pin "26") (pinfunction "3.3V_26") (pintype "passive"))
    )
    (net (code "107") (name "unconnected-(Q9-5-Pad7)") (class "Default")
      (node (ref "Q9") (pin "7") (pinfunction "5_7") (pintype "passive"))
    )
    (net (code "108") (name "unconnected-(Q9-8-Pad10)") (class "Default")
      (node (ref "Q9") (pin "10") (pinfunction "8_10") (pintype "passive"))
    )
    (net (code "109") (name "unconnected-(Q9-9-Pad11)") (class "Default")
      (node (ref "Q9") (pin "11") (pinfunction "9_11") (pintype "passive"))
    )
    (net (code "110") (name "unconnected-(Q9-14-Pad16)") (class "Default")
      (node (ref "Q9") (pin "16") (pinfunction "14_16") (pintype "passive"))
    )
    (net (code "111") (name "unconnected-(Q9-16-Pad18)") (class "Default")
      (node (ref "Q9") (pin "18") (pinfunction "16_18") (pintype "passive"))
    )
    (net (code "112") (name "unconnected-(Q9-17-Pad19)") (class "Default")
      (node (ref "Q9") (pin "19") (pinfunction "17_19") (pintype "passive"))
    )
    (net (code "113") (name "unconnected-(Q9-20-Pad22)") (class "Default")
      (node (ref "Q9") (pin "22") (pinfunction "20_22") (pintype "passive"))
    )
    (net (code "114") (name "unconnected-(Q9-22-Pad24)") (class "Default")
      (node (ref "Q9") (pin "24") (pinfunction "22_24") (pintype "passive"))
    )
    (net (code "115") (name "unconnected-(Q9-GND-Pad27)") (class "Default")
      (node (ref "Q9") (pin "27") (pinfunction "GND_27") (pintype "passive"))
    )
    (net (code "116") (name "unconnected-(R6-Pad2)") (class "Default")
      (node (ref "R6") (pin "2") (pinfunction "2_2") (pintype "passive"))
    )
    (net (code "117") (name "unconnected-(R6-Pad4)") (class "Default")
      (node (ref "R6") (pin "4") (pinfunction "4_4") (pintype "passive"))
    )
    (net (code "118") (name "unconnected-(R6-Pad5)") (class "Default")
      (node (ref "R6") (pin "5") (pinfunction "5_5") (pintype "passive"))
    )
    (net (code "119") (name "unconnected-(R6-Pad6)") (class "Default")
      (node (ref "R6") (pin "6") (pinfunction "6_6") (pintype "passive"))
    )
    (net (code "120") (name "unconnected-(R6-Pad7)") (class "Default")
      (node (ref "R6") (pin "7") (pinfunction "7_7") (pintype "passive"))
    )
    (net (code "121") (name "unconnected-(R6-Pad12)") (class "Default")
      (node (ref "R6") (pin "12") (pinfunction "12_12") (pintype "passive"))
    )
    (net (code "122") (name "unconnected-(R7-Pad2)") (class "Default")
      (node (ref "R7") (pin "2") (pinfunction "2_2") (pintype "passive"))
    )
    (net (code "123") (name "unconnected-(R7-Pad4)") (class "Default")
      (node (ref "R7") (pin "4") (pinfunction "4_4") (pintype "passive"))
    )
    (net (code "124") (name "unconnected-(R7-Pad5)") (class "Default")
      (node (ref "R7") (pin "5") (pinfunction "5_5") (pintype "passive"))
    )
    (net (code "125") (name "unconnected-(R7-Pad6)") (class "Default")
      (node (ref "R7") (pin "6") (pinfunction "6_6") (pintype "passive"))
    )
    (net (code "126") (name "unconnected-(R7-Pad7)") (class "Default")
      (node (ref "R7") (pin "7") (pinfunction "7_7") (pintype "passive"))
    )
    (net (code "127") (name "unconnected-(R7-Pad12)") (class "Default")
      (node (ref "R7") (pin "12") (pinfunction "12_12") (pintype "passive"))
    )
    (net (code "128") (name "unconnected-(S6-Pad4)") (class "Default")
      (node (ref "S6") (pin "4") (pinfunction "4_4") (pintype "passive"))
    )
    (net (code "129") (name "unconnected-(S6-Pad5)") (class "Default")
      (node (ref "S6") (pin "5") (pinfunction "5_5") (pintype "passive"))
    )
    (net (code "130") (name "unconnected-(T3-Pad1)") (class "Default")
      (node (ref "T3") (pin "1") (pinfunction "1_1") (pintype "passive"))
    )
    (net (code "131") (name "unconnected-(T4-Pad1)") (class "Default")
      (node (ref "T4") (pin "1") (pinfunction "1_1") (pintype "passive"))
    )
  )
)
